# Pot_Board1.net
KiCad netlist of a schematic drawn in Altium Designer
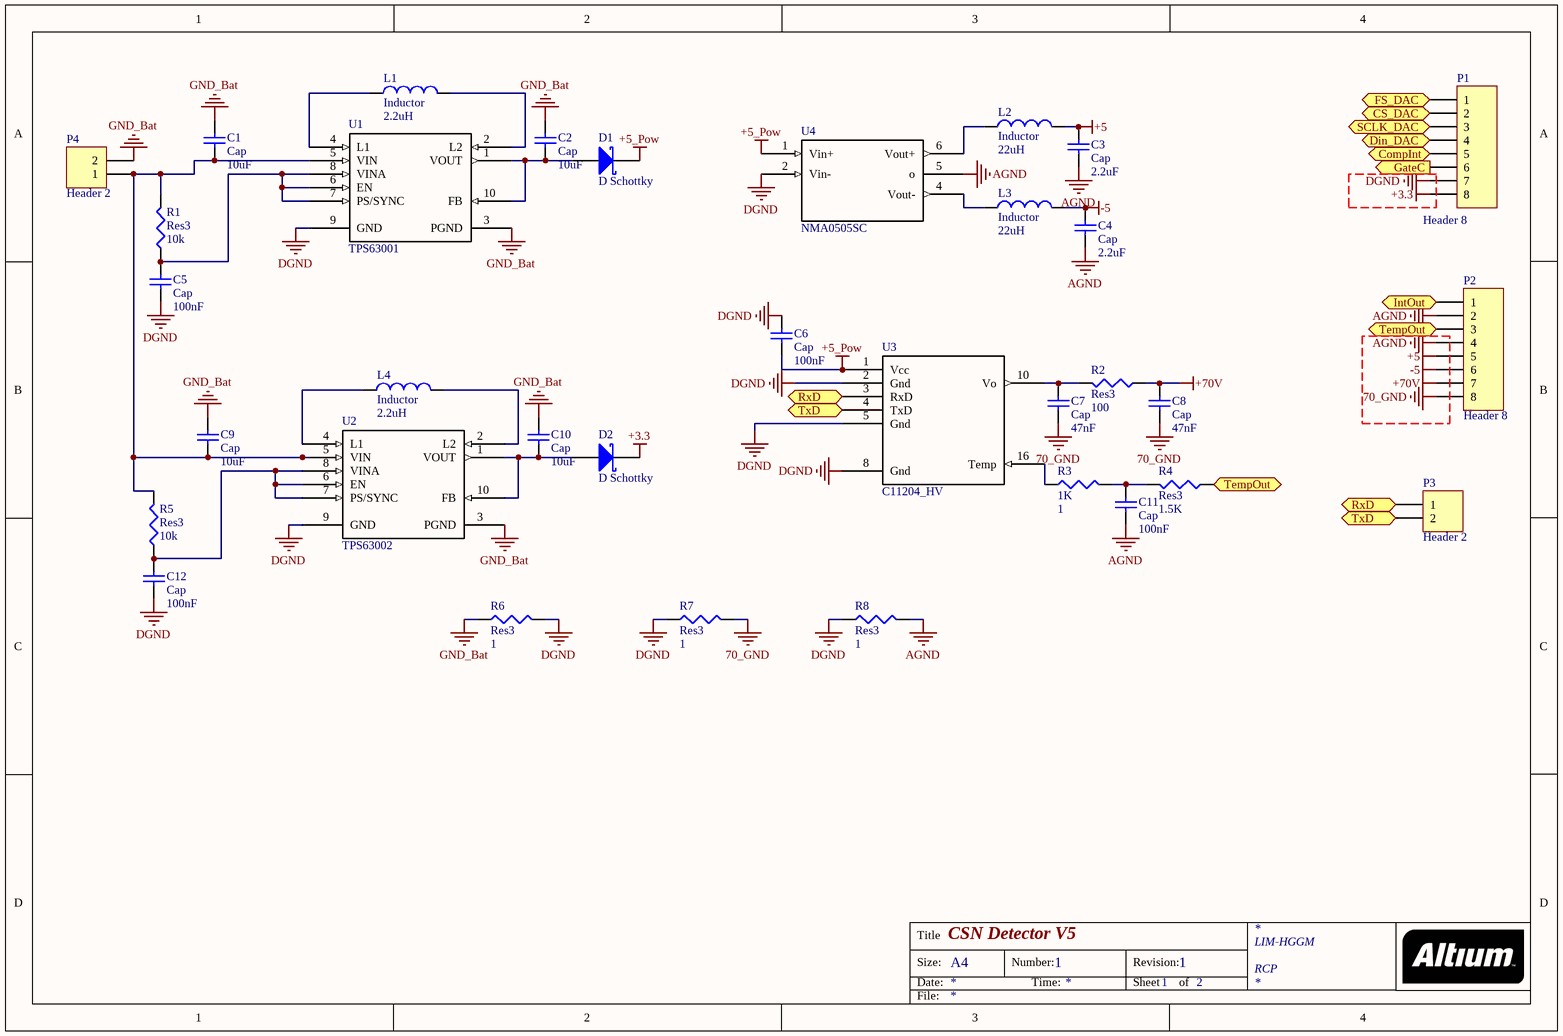
[diagram p0: Pot_Board1.SchDoc]

(export (version "E")
  (design (tool "Eeschema 10.0.6"))
  (components
    (comp (ref "C1")
      (value "Cap")
      (footprint "C0805")
      (description "Capacitor")
      (fields (field (name "ALTIUM_VALUE") "10uF") (field (name "PUBLISHER") "Altium Limited"))
      (libsource (lib "Miscellaneous Devices") (part "Cap"))
    )
    (comp (ref "C2")
      (value "Cap")
      (footprint "C0805")
      (description "Capacitor")
      (fields (field (name "ALTIUM_VALUE") "10uF") (field (name "PUBLISHER") "Altium Limited"))
      (libsource (lib "Miscellaneous Devices") (part "Cap"))
    )
    (comp (ref "C3")
      (value "Cap")
      (footprint "6-0805_N")
      (description "Capacitor")
      (fields (field (name "ALTIUM_VALUE") "2.2uF") (field (name "PUBLISHER") "Altium Limited"))
      (libsource (lib "Miscellaneous Devices") (part "Cap"))
    )
    (comp (ref "C4")
      (value "Cap")
      (footprint "6-0805_N")
      (description "Capacitor")
      (fields (field (name "ALTIUM_VALUE") "2.2uF") (field (name "PUBLISHER") "Altium Limited"))
      (libsource (lib "Miscellaneous Devices") (part "Cap"))
    )
    (comp (ref "C5")
      (value "Cap")
      (footprint "J1-0603")
      (description "Capacitor")
      (fields (field (name "ALTIUM_VALUE") "100nF") (field (name "PUBLISHER") "Altium Limited"))
      (libsource (lib "Miscellaneous Devices") (part "Cap"))
    )
    (comp (ref "C6")
      (value "Cap")
      (footprint "C0805")
      (description "Capacitor")
      (fields (field (name "ALTIUM_VALUE") "100nF") (field (name "PUBLISHER") "Altium Limited"))
      (libsource (lib "Miscellaneous Devices") (part "Cap"))
    )
    (comp (ref "C7")
      (value "Cap")
      (footprint "J1-0603")
      (description "Capacitor")
      (fields (field (name "ALTIUM_VALUE") "47nF") (field (name "PUBLISHER") "Altium Limited"))
      (libsource (lib "Miscellaneous Devices") (part "Cap"))
    )
    (comp (ref "C8")
      (value "Cap")
      (footprint "J1-0603")
      (description "Capacitor")
      (fields (field (name "ALTIUM_VALUE") "47nF") (field (name "PUBLISHER") "Altium Limited"))
      (libsource (lib "Miscellaneous Devices") (part "Cap"))
    )
    (comp (ref "C9")
      (value "Cap")
      (footprint "C0805")
      (description "Capacitor")
      (fields (field (name "ALTIUM_VALUE") "10uF") (field (name "PUBLISHER") "Altium Limited"))
      (libsource (lib "Miscellaneous Devices") (part "Cap"))
    )
    (comp (ref "C10")
      (value "Cap")
      (footprint "C0805")
      (description "Capacitor")
      (fields (field (name "ALTIUM_VALUE") "10uF") (field (name "PUBLISHER") "Altium Limited"))
      (libsource (lib "Miscellaneous Devices") (part "Cap"))
    )
    (comp (ref "C11")
      (value "Cap")
      (footprint "J1-0603")
      (description "Capacitor")
      (fields (field (name "ALTIUM_VALUE") "100nF") (field (name "PUBLISHER") "Altium Limited"))
      (libsource (lib "Miscellaneous Devices") (part "Cap"))
    )
    (comp (ref "C12")
      (value "Cap")
      (footprint "J1-0603")
      (description "Capacitor")
      (fields (field (name "ALTIUM_VALUE") "100nF") (field (name "PUBLISHER") "Altium Limited"))
      (libsource (lib "Miscellaneous Devices") (part "Cap"))
    )
    (comp (ref "D1")
      (value "D Schottky")
      (footprint "J1-0603")
      (description "Schottky Diode")
      (fields (field (name "PUBLISHER") "Altium Limited"))
      (libsource (lib "Miscellaneous Devices") (part "D Schottky"))
    )
    (comp (ref "D2")
      (value "D Schottky")
      (footprint "J1-0603")
      (description "Schottky Diode")
      (fields (field (name "PUBLISHER") "Altium Limited"))
      (libsource (lib "Miscellaneous Devices") (part "D Schottky"))
    )
    (comp (ref "L1")
      (value "Inductor")
      (footprint "C1210_L")
      (fields (field (name "ALTIUM_VALUE") "2.2uH") (field (name "PUBLISHER") "Altium Limited"))
      (libsource (lib "Miscellaneous Devices") (part "Inductor"))
    )
    (comp (ref "L2")
      (value "Inductor")
      (footprint "C1210")
      (fields (field (name "ALTIUM_VALUE") "22uH") (field (name "PUBLISHER") "Altium Limited"))
      (libsource (lib "Miscellaneous Devices") (part "Inductor"))
    )
    (comp (ref "L3")
      (value "Inductor")
      (footprint "C1210")
      (fields (field (name "ALTIUM_VALUE") "22uH") (field (name "PUBLISHER") "Altium Limited"))
      (libsource (lib "Miscellaneous Devices") (part "Inductor"))
    )
    (comp (ref "L4")
      (value "Inductor")
      (footprint "C1210_L")
      (fields (field (name "ALTIUM_VALUE") "2.2uH") (field (name "PUBLISHER") "Altium Limited"))
      (libsource (lib "Miscellaneous Devices") (part "Inductor"))
    )
    (comp (ref "P1")
      (value "Header 8")
      (footprint "HDR1X8")
      (description "Header, 8-Pin")
      (fields (field (name "PUBLISHER") "Altium Limited"))
      (libsource (lib "Miscellaneous Connectors") (part "Header 8"))
    )
    (comp (ref "P2")
      (value "Header 8")
      (footprint "HDR1X8")
      (description "Header, 8-Pin")
      (fields (field (name "PUBLISHER") "Altium Limited"))
      (libsource (lib "Miscellaneous Connectors") (part "Header 8"))
    )
    (comp (ref "P3")
      (value "Header 2")
      (footprint "HDR1X2")
      (description "Header, 2-Pin")
      (fields (field (name "PUBLISHER") "Altium Limited"))
      (libsource (lib "Miscellaneous Connectors") (part "Header 2"))
    )
    (comp (ref "P4")
      (value "Header 2")
      (footprint "HDR1X2")
      (description "Header, 2-Pin")
      (fields (field (name "PUBLISHER") "Altium Limited"))
      (libsource (lib "") (part "Header 2_1"))
    )
    (comp (ref "R1")
      (value "Res3")
      (footprint "J1-0603")
      (description "Resistor")
      (fields (field (name "ALTIUM_VALUE") "10k") (field (name "PUBLISHER") "Altium Limited"))
      (libsource (lib "Miscellaneous Devices") (part "Res3"))
    )
    (comp (ref "R2")
      (value "Res3")
      (footprint "J1-0603")
      (description "Resistor")
      (fields (field (name "ALTIUM_VALUE") "100") (field (name "PUBLISHER") "Altium Limited"))
      (libsource (lib "Miscellaneous Devices") (part "Res3"))
    )
    (comp (ref "R3")
      (value "1K")
      (footprint "J1-0603")
      (description "Resistor")
      (fields (field (name "ALTIUM_VALUE") "1") (field (name "PUBLISHER") "Altium Limited"))
      (libsource (lib "Miscellaneous Devices") (part "Res3"))
    )
    (comp (ref "R4")
      (value "Res3")
      (footprint "J1-0603")
      (description "Resistor")
      (fields (field (name "ALTIUM_VALUE") "1.5K") (field (name "PUBLISHER") "Altium Limited"))
      (libsource (lib "Miscellaneous Devices") (part "Res3"))
    )
    (comp (ref "R5")
      (value "Res3")
      (footprint "J1-0603")
      (description "Resistor")
      (fields (field (name "ALTIUM_VALUE") "10k") (field (name "PUBLISHER") "Altium Limited"))
      (libsource (lib "Miscellaneous Devices") (part "Res3"))
    )
    (comp (ref "R6")
      (value "Res3")
      (footprint "J1-0603")
      (description "Resistor")
      (fields (field (name "ALTIUM_VALUE") "1") (field (name "PUBLISHER") "Altium Limited"))
      (libsource (lib "Miscellaneous Devices") (part "Res3"))
    )
    (comp (ref "R7")
      (value "Res3")
      (footprint "J1-0603")
      (description "Resistor")
      (fields (field (name "ALTIUM_VALUE") "1") (field (name "PUBLISHER") "Altium Limited"))
      (libsource (lib "Miscellaneous Devices") (part "Res3"))
    )
    (comp (ref "R8")
      (value "Res3")
      (footprint "J1-0603")
      (description "Resistor")
      (fields (field (name "ALTIUM_VALUE") "1") (field (name "PUBLISHER") "Altium Limited"))
      (libsource (lib "Miscellaneous Devices") (part "Res3"))
    )
    (comp (ref "U1")
      (value "TPS63001")
      (footprint "DRC10_2P4X1P65")
      (description "Imported")
      (fields
        (field (name "MANUFACTURER_PART_NUMBER") "tps63001_drc_10")
        (field (name "MANUFACTURER") "Texas Instruments")
      )
      (libsource (lib "Int_Lib1") (part "TPS63001_DRC_10"))
    )
    (comp (ref "U2")
      (value "TPS63002")
      (footprint "DRC10_2P4X1P65")
      (description "Imported")
      (fields
        (field (name "MANUFACTURER_PART_NUMBER") "tps63001_drc_10")
        (field (name "GENERIC_PART_NUMBER") "TPS63001")
      )
      (libsource (lib "Int_Lib1") (part "TPS63001_DRC_10"))
    )
    (comp (ref "U3")
      (value "C11204_HV")
      (footprint "C11204_HAM")
      (libsource (lib "Int_Lib1") (part "C11204_HV"))
    )
    (comp (ref "U4")
      (value "NMA0505SC")
      (footprint "NMA0505SC_SIP")
      (libsource (lib "Int_Lib1") (part "NMA0505SC"))
    )
  )
  (nets
    (net (code "1") (name "+3.3") (class "Default")
      (node (ref "D2") (pin "2") (pinfunction "K_2") (pintype "passive"))
      (node (ref "P1") (pin "8") (pinfunction "8_8") (pintype "passive"))
    )
    (net (code "2") (name "+5") (class "Default")
      (node (ref "C3") (pin "1") (pinfunction "1_1") (pintype "passive"))
      (node (ref "L2") (pin "2") (pinfunction "2_2") (pintype "passive"))
      (node (ref "P2") (pin "5") (pinfunction "5_5") (pintype "passive"))
    )
    (net (code "3") (name "+5_Pow") (class "Default")
      (node (ref "C6") (pin "2") (pinfunction "2_2") (pintype "passive"))
      (node (ref "D1") (pin "2") (pinfunction "K_2") (pintype "passive"))
      (node (ref "U3") (pin "1") (pinfunction "Vcc_1") (pintype "power_in"))
      (node (ref "U4") (pin "1") (pinfunction "Vin+_1") (pintype "input"))
    )
    (net (code "4") (name "+70V") (class "Default")
      (node (ref "C8") (pin "2") (pinfunction "2_2") (pintype "passive"))
      (node (ref "P2") (pin "7") (pinfunction "7_7") (pintype "passive"))
      (node (ref "R2") (pin "1") (pinfunction "1_1") (pintype "passive"))
    )
    (net (code "5") (name "-5") (class "Default")
      (node (ref "C4") (pin "2") (pinfunction "2_2") (pintype "passive"))
      (node (ref "L3") (pin "2") (pinfunction "2_2") (pintype "passive"))
      (node (ref "P2") (pin "6") (pinfunction "6_6") (pintype "passive"))
    )
    (net (code "6") (name "/CS_DAC") (class "Default")
      (node (ref "P1") (pin "2") (pinfunction "2_2") (pintype "passive"))
    )
    (net (code "7") (name "/CompInt") (class "Default")
      (node (ref "P1") (pin "5") (pinfunction "5_5") (pintype "passive"))
    )
    (net (code "8") (name "/Din_DAC") (class "Default")
      (node (ref "P1") (pin "4") (pinfunction "4_4") (pintype "passive"))
    )
    (net (code "9") (name "/FS_DAC") (class "Default")
      (node (ref "P1") (pin "1") (pinfunction "1_1") (pintype "passive"))
    )
    (net (code "10") (name "/GateC") (class "Default")
      (node (ref "P1") (pin "6") (pinfunction "6_6") (pintype "passive"))
    )
    (net (code "11") (name "/IntOut") (class "Default")
      (node (ref "P2") (pin "1") (pinfunction "1_1") (pintype "passive"))
    )
    (net (code "12") (name "/RxD") (class "Default")
      (node (ref "P3") (pin "1") (pinfunction "1_1") (pintype "passive"))
      (node (ref "U3") (pin "3") (pinfunction "RxD_3") (pintype "passive"))
    )
    (net (code "13") (name "/SCLK_DAC") (class "Default")
      (node (ref "P1") (pin "3") (pinfunction "3_3") (pintype "passive"))
    )
    (net (code "14") (name "/TempOut") (class "Default")
      (node (ref "P2") (pin "3") (pinfunction "3_3") (pintype "passive"))
      (node (ref "R4") (pin "1") (pinfunction "1_1") (pintype "passive"))
    )
    (net (code "15") (name "/TxD") (class "Default")
      (node (ref "P3") (pin "2") (pinfunction "2_2") (pintype "passive"))
      (node (ref "U3") (pin "4") (pinfunction "TxD_4") (pintype "passive"))
    )
    (net (code "16") (name "70_GND") (class "Default")
      (node (ref "C7") (pin "1") (pinfunction "1_1") (pintype "passive"))
      (node (ref "C8") (pin "1") (pinfunction "1_1") (pintype "passive"))
      (node (ref "P2") (pin "8") (pinfunction "8_8") (pintype "passive"))
      (node (ref "R7") (pin "2") (pinfunction "2_2") (pintype "passive"))
    )
    (net (code "17") (name "AGND") (class "Default")
      (node (ref "C11") (pin "1") (pinfunction "1_1") (pintype "passive"))
      (node (ref "C3") (pin "2") (pinfunction "2_2") (pintype "passive"))
      (node (ref "C4") (pin "1") (pinfunction "1_1") (pintype "passive"))
      (node (ref "P2") (pin "2") (pinfunction "2_2") (pintype "passive"))
      (node (ref "P2") (pin "4") (pinfunction "4_4") (pintype "passive"))
      (node (ref "R8") (pin "2") (pinfunction "2_2") (pintype "passive"))
      (node (ref "U4") (pin "5") (pinfunction "o_5") (pintype "power_in"))
    )
    (net (code "18") (name "DGND") (class "Default")
      (node (ref "C12") (pin "2") (pinfunction "2_2") (pintype "passive"))
      (node (ref "C5") (pin "2") (pinfunction "2_2") (pintype "passive"))
      (node (ref "C6") (pin "1") (pinfunction "1_1") (pintype "passive"))
      (node (ref "P1") (pin "7") (pinfunction "7_7") (pintype "passive"))
      (node (ref "R6") (pin "2") (pinfunction "2_2") (pintype "passive"))
      (node (ref "R7") (pin "1") (pinfunction "1_1") (pintype "passive"))
      (node (ref "R8") (pin "1") (pinfunction "1_1") (pintype "passive"))
      (node (ref "U1") (pin "9") (pinfunction "GND_9") (pintype "power_in"))
      (node (ref "U2") (pin "9") (pinfunction "GND_9") (pintype "power_in"))
      (node (ref "U3") (pin "2") (pinfunction "Gnd_2") (pintype "passive"))
      (node (ref "U3") (pin "5") (pinfunction "Gnd_5") (pintype "power_in"))
      (node (ref "U3") (pin "8") (pinfunction "Gnd_8") (pintype "power_in"))
      (node (ref "U4") (pin "2") (pinfunction "Vin-_2") (pintype "input"))
    )
    (net (code "19") (name "GND_Bat") (class "Default")
      (node (ref "C1") (pin "2") (pinfunction "2_2") (pintype "passive"))
      (node (ref "C10") (pin "2") (pinfunction "2_2") (pintype "passive"))
      (node (ref "C2") (pin "2") (pinfunction "2_2") (pintype "passive"))
      (node (ref "C9") (pin "2") (pinfunction "2_2") (pintype "passive"))
      (node (ref "P4") (pin "2") (pinfunction "2_2") (pintype "passive"))
      (node (ref "R6") (pin "1") (pinfunction "1_1") (pintype "passive"))
      (node (ref "U1") (pin "3") (pinfunction "PGND_3") (pintype "power_in"))
      (node (ref "U2") (pin "3") (pinfunction "PGND_3") (pintype "power_in"))
    )
    (net (code "20") (name "Net-(C11-Pad2)") (class "Default")
      (node (ref "C11") (pin "2") (pinfunction "2_2") (pintype "passive"))
      (node (ref "R3") (pin "2") (pinfunction "2_2") (pintype "passive"))
      (node (ref "R4") (pin "2") (pinfunction "2_2") (pintype "passive"))
    )
    (net (code "21") (name "Net-(D1-A)") (class "Default")
      (node (ref "C2") (pin "1") (pinfunction "1_1") (pintype "passive"))
      (node (ref "D1") (pin "1") (pinfunction "A_1") (pintype "passive"))
      (node (ref "U1") (pin "1") (pinfunction "VOUT_1") (pintype "output"))
      (node (ref "U1") (pin "10") (pinfunction "FB_10") (pintype "input"))
    )
    (net (code "22") (name "Net-(D2-A)") (class "Default")
      (node (ref "C10") (pin "1") (pinfunction "1_1") (pintype "passive"))
      (node (ref "D2") (pin "1") (pinfunction "A_1") (pintype "passive"))
      (node (ref "U2") (pin "1") (pinfunction "VOUT_1") (pintype "output"))
      (node (ref "U2") (pin "10") (pinfunction "FB_10") (pintype "input"))
    )
    (net (code "23") (name "Net-(U1-EN)") (class "Default")
      (node (ref "C5") (pin "1") (pinfunction "1_1") (pintype "passive"))
      (node (ref "R1") (pin "1") (pinfunction "1_1") (pintype "passive"))
      (node (ref "U1") (pin "6") (pinfunction "EN_6") (pintype "input"))
      (node (ref "U1") (pin "7") (pinfunction "PS/SYNC_7") (pintype "input"))
      (node (ref "U1") (pin "8") (pinfunction "VINA_8") (pintype "input"))
    )
    (net (code "24") (name "Net-(U1-L1)") (class "Default")
      (node (ref "L1") (pin "1") (pinfunction "1_1") (pintype "passive"))
      (node (ref "U1") (pin "4") (pinfunction "L1_4") (pintype "input"))
    )
    (net (code "25") (name "Net-(U1-L2)") (class "Default")
      (node (ref "L1") (pin "2") (pinfunction "2_2") (pintype "passive"))
      (node (ref "U1") (pin "2") (pinfunction "L2_2") (pintype "input"))
    )
    (net (code "26") (name "Net-(U1-VIN)") (class "Default")
      (node (ref "C1") (pin "1") (pinfunction "1_1") (pintype "passive"))
      (node (ref "C9") (pin "1") (pinfunction "1_1") (pintype "passive"))
      (node (ref "P4") (pin "1") (pinfunction "1_1") (pintype "passive"))
      (node (ref "R1") (pin "2") (pinfunction "2_2") (pintype "passive"))
      (node (ref "R5") (pin "2") (pinfunction "2_2") (pintype "passive"))
      (node (ref "U1") (pin "5") (pinfunction "VIN_5") (pintype "input"))
      (node (ref "U2") (pin "5") (pinfunction "VIN_5") (pintype "input"))
    )
    (net (code "27") (name "Net-(U2-EN)") (class "Default")
      (node (ref "C12") (pin "1") (pinfunction "1_1") (pintype "passive"))
      (node (ref "R5") (pin "1") (pinfunction "1_1") (pintype "passive"))
      (node (ref "U2") (pin "6") (pinfunction "EN_6") (pintype "input"))
      (node (ref "U2") (pin "7") (pinfunction "PS/SYNC_7") (pintype "input"))
      (node (ref "U2") (pin "8") (pinfunction "VINA_8") (pintype "input"))
    )
    (net (code "28") (name "Net-(U2-L1)") (class "Default")
      (node (ref "L4") (pin "1") (pinfunction "1_1") (pintype "passive"))
      (node (ref "U2") (pin "4") (pinfunction "L1_4") (pintype "input"))
    )
    (net (code "29") (name "Net-(U2-L2)") (class "Default")
      (node (ref "L4") (pin "2") (pinfunction "2_2") (pintype "passive"))
      (node (ref "U2") (pin "2") (pinfunction "L2_2") (pintype "input"))
    )
    (net (code "30") (name "Net-(U3-Temp)") (class "Default")
      (node (ref "R3") (pin "1") (pinfunction "1_1") (pintype "passive"))
      (node (ref "U3") (pin "16") (pinfunction "Temp_16") (pintype "input"))
    )
    (net (code "31") (name "Net-(U3-Vo)") (class "Default")
      (node (ref "C7") (pin "2") (pinfunction "2_2") (pintype "passive"))
      (node (ref "R2") (pin "2") (pinfunction "2_2") (pintype "passive"))
      (node (ref "U3") (pin "10") (pinfunction "Vo_10") (pintype "output"))
    )
    (net (code "32") (name "Net-(U4-Vout+)") (class "Default")
      (node (ref "L2") (pin "1") (pinfunction "1_1") (pintype "passive"))
      (node (ref "U4") (pin "6") (pinfunction "Vout+_6") (pintype "output"))
    )
    (net (code "33") (name "Net-(U4-Vout-)") (class "Default")
      (node (ref "L3") (pin "1") (pinfunction "1_1") (pintype "passive"))
      (node (ref "U4") (pin "4") (pinfunction "Vout-_4") (pintype "output"))
    )
    (net (code "34") (name "unconnected-(U3-HV-Pad7)") (class "Default")
      (node (ref "U3") (pin "7") (pinfunction "HV_7") (pintype "passive"))
    )
    (net (code "35") (name "unconnected-(U3-NC-Pad6)") (class "Default")
      (node (ref "U3") (pin "6") (pinfunction "NC_6") (pintype "passive"))
    )
    (net (code "36") (name "unconnected-(U3-NC-Pad9)") (class "Default")
      (node (ref "U3") (pin "9") (pinfunction "NC_9") (pintype "passive"))
    )
    (net (code "37") (name "unconnected-(U3-NC-Pad11)") (class "Default")
      (node (ref "U3") (pin "11") (pinfunction "NC_11") (pintype "passive"))
    )
    (net (code "38") (name "unconnected-(U3-NC-Pad12)") (class "Default")
      (node (ref "U3") (pin "12") (pinfunction "NC_12") (pintype "passive"))
    )
    (net (code "39") (name "unconnected-(U3-NC-Pad13)") (class "Default")
      (node (ref "U3") (pin "13") (pinfunction "NC_13") (pintype "passive"))
    )
    (net (code "40") (name "unconnected-(U3-NC-Pad14)") (class "Default")
      (node (ref "U3") (pin "14") (pinfunction "NC_14") (pintype "passive"))
    )
    (net (code "41") (name "unconnected-(U3-NC-Pad15)") (class "Default")
      (node (ref "U3") (pin "15") (pinfunction "NC_15") (pintype "passive"))
    )
  )
)
